# SparkFun_RTK_Facet_-_External_Connector.net
KiCad netlist of a schematic drawn in EAGLE
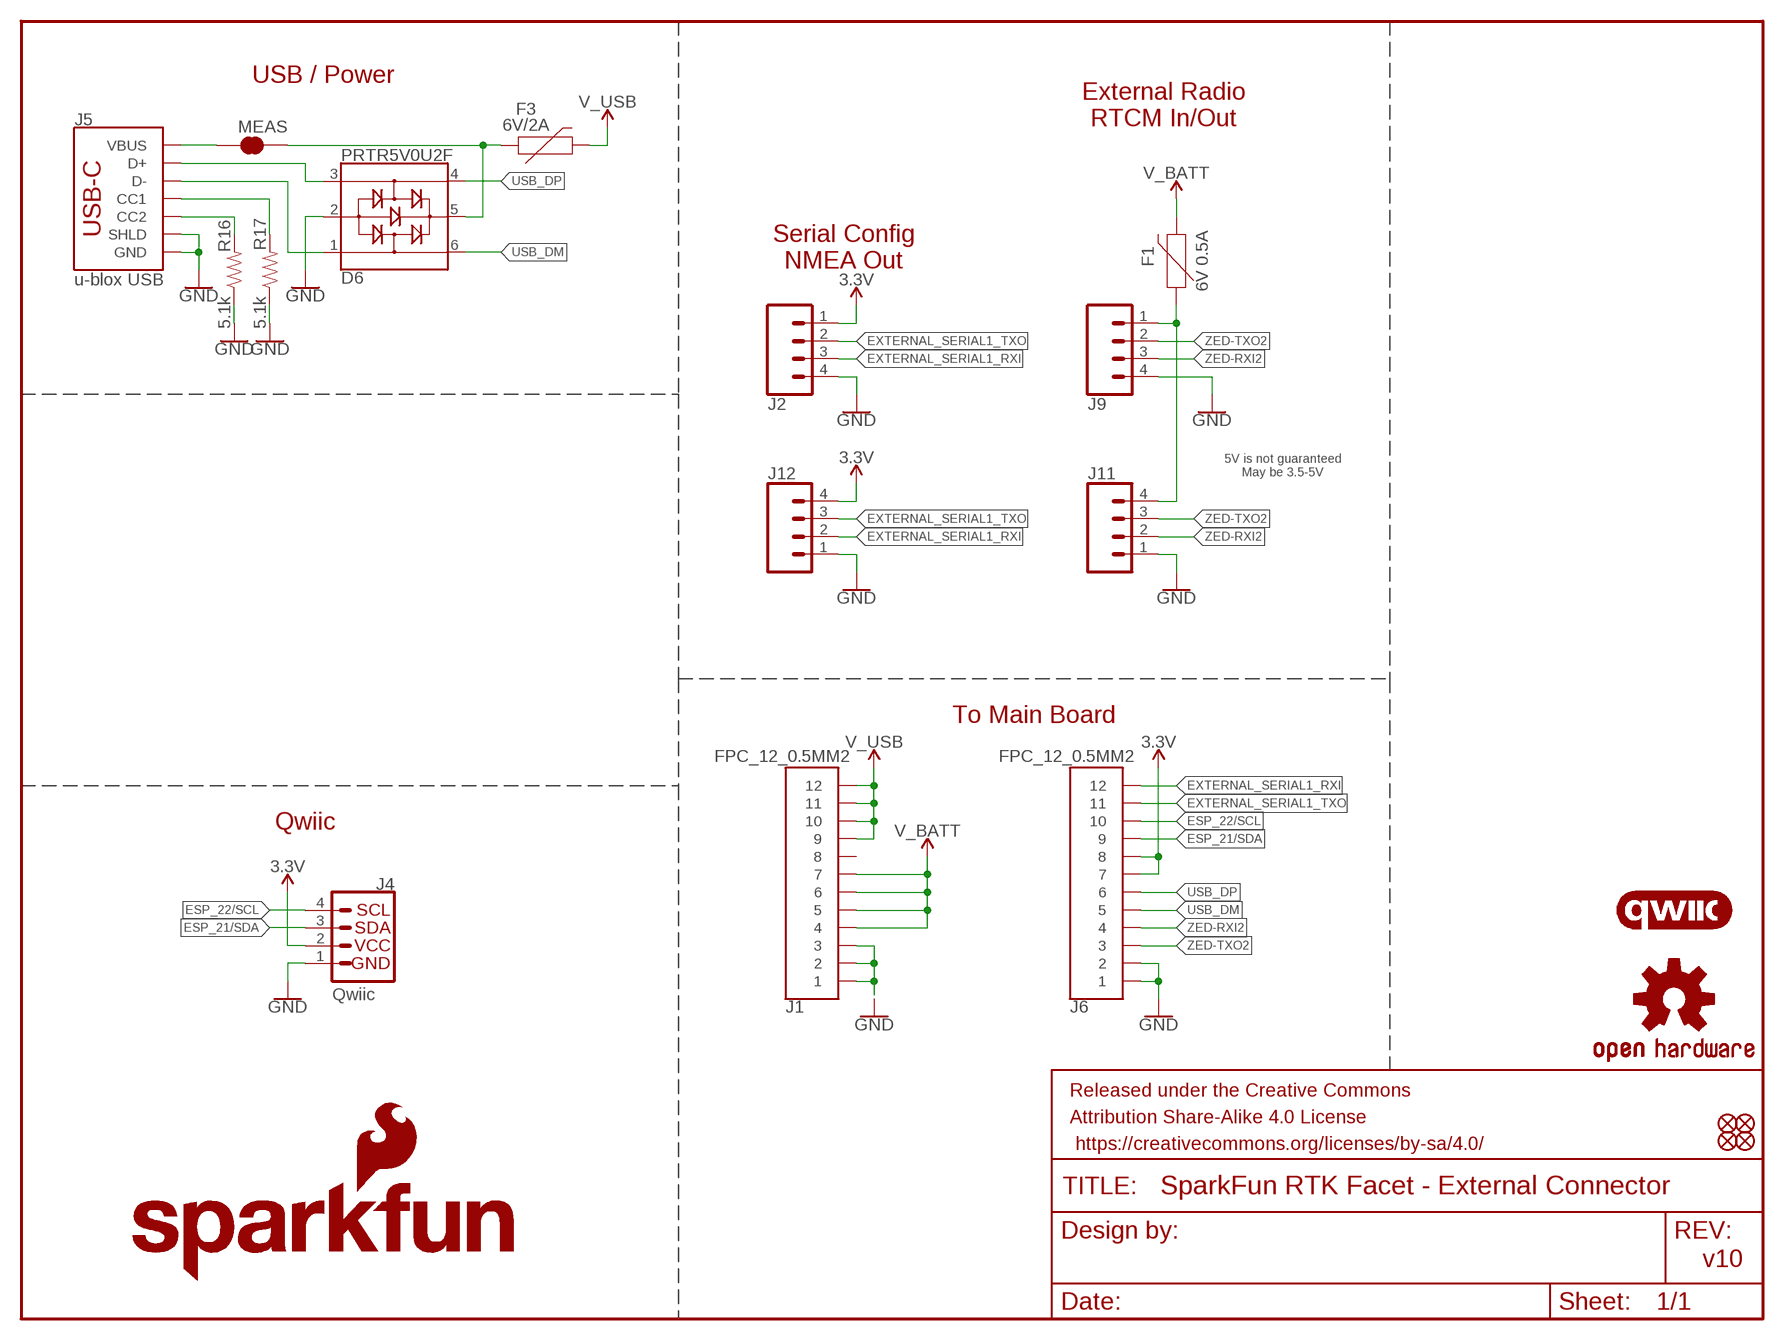
[diagram p0: schematic, sheet 1]

(export (version "E")
  (design (tool "Eeschema 10.0.6"))
  (components
    (comp (ref "D6")
      (value "PRTR5V0U2F")
      (footprint "eagle-import:SOT886")
      (libsource (lib "eagle-import") (part "PRTR5V0U2F"))
    )
    (comp (ref "F1")
      (value "6V 0.5A")
      (footprint "eagle-import:0805")
      (libsource (lib "eagle-import") (part "PPTC_6V500MA"))
    )
    (comp (ref "F3")
      (value "6V/2A")
      (footprint "eagle-import:1210")
      (libsource (lib "eagle-import") (part "PPTC_6V2A"))
    )
    (comp (ref "FRAME1")
      (value "FRAME-LETTER")
      (footprint "eagle-import:CREATIVE_COMMONS")
      (libsource (lib "eagle-import") (part "FRAME-LETTER"))
    )
    (comp (ref "J1")
      (value "FPC_12_0.5MM2")
      (footprint "eagle-import:FPC_12_FLIP_DOUBLESIDED_2")
      (libsource (lib "eagle-import") (part "FPC_12_0.5MM2"))
    )
    (comp (ref "J2")
      (value "CONN_04JST-SMD-LOCKING")
      (footprint "eagle-import:JST-4-SMD-1.25MM-LOCKING")
      (libsource (lib "eagle-import") (part "CONN_04JST-SMD-LOCKING"))
    )
    (comp (ref "J4")
      (value "Qwiic")
      (footprint "eagle-import:JST04_1MM_RA")
      (libsource (lib "eagle-import") (part "I2C_STANDARDQWIIC"))
    )
    (comp (ref "J5")
      (value "u-blox USB")
      (footprint "eagle-import:USB-C-16P-2LAYER-PADS")
      (libsource (lib "eagle-import") (part "USB_C_2-LAYER_PADS"))
    )
    (comp (ref "J6")
      (value "FPC_12_0.5MM2")
      (footprint "eagle-import:FPC_12_FLIP_DOUBLESIDED_2")
      (libsource (lib "eagle-import") (part "FPC_12_0.5MM2"))
    )
    (comp (ref "J9")
      (value "CONN_04JST-SMD-LOCKING")
      (footprint "eagle-import:JST-4-SMD-1.25MM-LOCKING")
      (libsource (lib "eagle-import") (part "CONN_04JST-SMD-LOCKING"))
    )
    (comp (ref "J11")
      (value "CONN_041X04_NO_SILK_NO_POP")
      (footprint "eagle-import:1X04_NO_SILK")
      (libsource (lib "eagle-import") (part "CONN_041X04_NO_SILK_NO_POP"))
    )
    (comp (ref "J12")
      (value "CONN_041X04_NO_SILK_NO_POP")
      (footprint "eagle-import:1X04_NO_SILK")
      (libsource (lib "eagle-import") (part "CONN_041X04_NO_SILK_NO_POP"))
    )
    (comp (ref "JP21")
      (value "FIDUCIALUFIDUCIAL")
      (footprint "eagle-import:FIDUCIAL-MICRO")
      (libsource (lib "eagle-import") (part "FIDUCIALUFIDUCIAL"))
    )
    (comp (ref "JP61")
      (value "FIDUCIALUFIDUCIAL")
      (footprint "eagle-import:FIDUCIAL-MICRO")
      (libsource (lib "eagle-import") (part "FIDUCIALUFIDUCIAL"))
    )
    (comp (ref "JP71")
      (value "FIDUCIALUFIDUCIAL")
      (footprint "eagle-import:FIDUCIAL-MICRO")
      (libsource (lib "eagle-import") (part "FIDUCIALUFIDUCIAL"))
    )
    (comp (ref "JP81")
      (value "FIDUCIALUFIDUCIAL")
      (footprint "eagle-import:FIDUCIAL-MICRO")
      (libsource (lib "eagle-import") (part "FIDUCIALUFIDUCIAL"))
    )
    (comp (ref "LOGO1")
      (value "OSHW-LOGOMINI")
      (footprint "eagle-import:OSHW-LOGO-MINI")
      (libsource (lib "eagle-import") (part "OSHW-LOGOMINI"))
    )
    (comp (ref "LOGO2")
      (value "SFE_LOGO_NAME_FLAME.1_INCH")
      (footprint "eagle-import:SFE_LOGO_NAME_FLAME_.1")
      (libsource (lib "eagle-import") (part "SFE_LOGO_NAME_FLAME.1_INCH"))
    )
    (comp (ref "LOGO3")
      (value "QWIIC_LOGO_CONNECTOR")
      (footprint "eagle-import:QWIIC_5.5MM")
      (libsource (lib "eagle-import") (part "QWIIC_LOGO_CONNECTOR"))
    )
    (comp (ref "MEAS")
      (value "JUMPER-COMBO_2_NC_TRACE")
      (footprint "eagle-import:COMBO-JUMPER_2_NC_TRACE")
      (libsource (lib "eagle-import") (part "JUMPER-COMBO_2_NC_TRACE"))
    )
    (comp (ref "R16")
      (value "5.1k")
      (footprint "eagle-import:0603")
      (libsource (lib "eagle-import") (part "5.1KOHM5.1KOHM-0603-1/10W-1%"))
    )
    (comp (ref "R17")
      (value "5.1k")
      (footprint "eagle-import:0603")
      (libsource (lib "eagle-import") (part "5.1KOHM5.1KOHM-0603-1/10W-1%"))
    )
  )
  (nets
    (net (code "1") (name "3.3V") (class "Default")
      (node (ref "J12") (pin "4") (pinfunction "4_4") (pintype "passive"))
      (node (ref "J2") (pin "1") (pinfunction "1_1") (pintype "passive"))
      (node (ref "J4") (pin "2") (pinfunction "2_2") (pintype "power_in"))
      (node (ref "J6") (pin "7") (pinfunction "7_7") (pintype "bidirectional"))
      (node (ref "J6") (pin "8") (pinfunction "8_8") (pintype "bidirectional"))
    )
    (net (code "2") (name "ESP_21{slash}SDA") (class "Default")
      (node (ref "J4") (pin "3") (pinfunction "3_3") (pintype "passive"))
      (node (ref "J6") (pin "9") (pinfunction "9_9") (pintype "bidirectional"))
    )
    (net (code "3") (name "ESP_22{slash}SCL") (class "Default")
      (node (ref "J4") (pin "4") (pinfunction "4_4") (pintype "passive"))
      (node (ref "J6") (pin "10") (pinfunction "10_10") (pintype "bidirectional"))
    )
    (net (code "4") (name "EXTERNAL_SERIAL1_RXI") (class "Default")
      (node (ref "J12") (pin "2") (pinfunction "2_2") (pintype "passive"))
      (node (ref "J2") (pin "3") (pinfunction "3_3") (pintype "passive"))
      (node (ref "J6") (pin "12") (pinfunction "12_12") (pintype "bidirectional"))
    )
    (net (code "5") (name "EXTERNAL_SERIAL1_TXO") (class "Default")
      (node (ref "J12") (pin "3") (pinfunction "3_3") (pintype "passive"))
      (node (ref "J2") (pin "2") (pinfunction "2_2") (pintype "passive"))
      (node (ref "J6") (pin "11") (pinfunction "11_11") (pintype "bidirectional"))
    )
    (net (code "6") (name "GND") (class "Default")
      (node (ref "D6") (pin "2") (pinfunction "2_2") (pintype "power_in"))
      (node (ref "J1") (pin "1") (pinfunction "1_1") (pintype "bidirectional"))
      (node (ref "J1") (pin "2") (pinfunction "2_2") (pintype "bidirectional"))
      (node (ref "J1") (pin "3") (pinfunction "3_3") (pintype "bidirectional"))
      (node (ref "J11") (pin "1") (pinfunction "1_1") (pintype "passive"))
      (node (ref "J12") (pin "1") (pinfunction "1_1") (pintype "passive"))
      (node (ref "J2") (pin "4") (pinfunction "4_4") (pintype "passive"))
      (node (ref "J4") (pin "1") (pinfunction "1_1") (pintype "power_in"))
      (node (ref "J5") (pin "GND") (pinfunction "GND_GND") (pintype "bidirectional"))
      (node (ref "J5") (pin "GND2") (pinfunction "GND_GND2") (pintype "bidirectional"))
      (node (ref "J5") (pin "SHLD1") (pinfunction "SHLD_SHLD1") (pintype "bidirectional"))
      (node (ref "J5") (pin "SHLD2") (pinfunction "SHLD_SHLD2") (pintype "bidirectional"))
      (node (ref "J5") (pin "SHLD3") (pinfunction "SHLD_SHLD3") (pintype "bidirectional"))
      (node (ref "J5") (pin "SHLD4") (pinfunction "SHLD_SHLD4") (pintype "bidirectional"))
      (node (ref "J6") (pin "1") (pinfunction "1_1") (pintype "bidirectional"))
      (node (ref "J6") (pin "2") (pinfunction "2_2") (pintype "bidirectional"))
      (node (ref "J9") (pin "4") (pinfunction "4_4") (pintype "passive"))
      (node (ref "R16") (pin "1") (pinfunction "1_1") (pintype "passive"))
      (node (ref "R17") (pin "1") (pinfunction "1_1") (pintype "passive"))
    )
    (net (code "7") (name "Net-(D6-Pad1)") (class "Default")
      (node (ref "D6") (pin "1") (pinfunction "1_1") (pintype "bidirectional"))
      (node (ref "J5") (pin "A7") (pinfunction "D-_A7") (pintype "bidirectional"))
      (node (ref "J5") (pin "B7") (pinfunction "D-_B7") (pintype "bidirectional"))
    )
    (net (code "8") (name "Net-(D6-Pad3)") (class "Default")
      (node (ref "D6") (pin "3") (pinfunction "3_3") (pintype "bidirectional"))
      (node (ref "J5") (pin "A6") (pinfunction "D+_A6") (pintype "bidirectional"))
      (node (ref "J5") (pin "B6") (pinfunction "D+_B6") (pintype "bidirectional"))
    )
    (net (code "9") (name "Net-(D6-Pad5)") (class "Default")
      (node (ref "D6") (pin "5") (pinfunction "5_5") (pintype "power_in"))
      (node (ref "F3") (pin "1") (pinfunction "1_1") (pintype "bidirectional"))
      (node (ref "MEAS") (pin "2") (pinfunction "2_2") (pintype "passive"))
      (node (ref "MEAS") (pin "4") (pinfunction "2_4") (pintype "passive"))
    )
    (net (code "10") (name "Net-(F1-Pad1)") (class "Default")
      (node (ref "F1") (pin "1") (pinfunction "1_1") (pintype "bidirectional"))
      (node (ref "J11") (pin "4") (pinfunction "4_4") (pintype "passive"))
      (node (ref "J9") (pin "1") (pinfunction "1_1") (pintype "passive"))
    )
    (net (code "11") (name "Net-(J5-CC1)") (class "Default")
      (node (ref "J5") (pin "A5") (pinfunction "CC1_A5") (pintype "bidirectional"))
      (node (ref "R17") (pin "2") (pinfunction "2_2") (pintype "passive"))
    )
    (net (code "12") (name "Net-(J5-CC2)") (class "Default")
      (node (ref "J5") (pin "B5") (pinfunction "CC2_B5") (pintype "bidirectional"))
      (node (ref "R16") (pin "2") (pinfunction "2_2") (pintype "passive"))
    )
    (net (code "13") (name "Net-(J5-VBUS-PadVBUS1)") (class "Default")
      (node (ref "J5") (pin "VBUS1") (pinfunction "VBUS_VBUS1") (pintype "bidirectional"))
      (node (ref "J5") (pin "VBUS2") (pinfunction "VBUS_VBUS2") (pintype "bidirectional"))
      (node (ref "MEAS") (pin "1") (pinfunction "1_1") (pintype "passive"))
      (node (ref "MEAS") (pin "3") (pinfunction "1_3") (pintype "passive"))
    )
    (net (code "14") (name "USB_DM") (class "Default")
      (node (ref "D6") (pin "6") (pinfunction "6_6") (pintype "bidirectional"))
      (node (ref "J6") (pin "5") (pinfunction "5_5") (pintype "bidirectional"))
    )
    (net (code "15") (name "USB_DP") (class "Default")
      (node (ref "D6") (pin "4") (pinfunction "4_4") (pintype "bidirectional"))
      (node (ref "J6") (pin "6") (pinfunction "6_6") (pintype "bidirectional"))
    )
    (net (code "16") (name "V_BATT") (class "Default")
      (node (ref "F1") (pin "2") (pinfunction "2_2") (pintype "bidirectional"))
      (node (ref "J1") (pin "4") (pinfunction "4_4") (pintype "bidirectional"))
      (node (ref "J1") (pin "5") (pinfunction "5_5") (pintype "bidirectional"))
      (node (ref "J1") (pin "6") (pinfunction "6_6") (pintype "bidirectional"))
      (node (ref "J1") (pin "7") (pinfunction "7_7") (pintype "bidirectional"))
    )
    (net (code "17") (name "V_USB") (class "Default")
      (node (ref "F3") (pin "2") (pinfunction "2_2") (pintype "bidirectional"))
      (node (ref "J1") (pin "10") (pinfunction "10_10") (pintype "bidirectional"))
      (node (ref "J1") (pin "11") (pinfunction "11_11") (pintype "bidirectional"))
      (node (ref "J1") (pin "12") (pinfunction "12_12") (pintype "bidirectional"))
      (node (ref "J1") (pin "9") (pinfunction "9_9") (pintype "bidirectional"))
    )
    (net (code "18") (name "ZED-RXI2") (class "Default")
      (node (ref "J11") (pin "2") (pinfunction "2_2") (pintype "passive"))
      (node (ref "J6") (pin "4") (pinfunction "4_4") (pintype "bidirectional"))
      (node (ref "J9") (pin "3") (pinfunction "3_3") (pintype "passive"))
    )
    (net (code "19") (name "ZED-TXO2") (class "Default")
      (node (ref "J11") (pin "3") (pinfunction "3_3") (pintype "passive"))
      (node (ref "J6") (pin "3") (pinfunction "3_3") (pintype "bidirectional"))
      (node (ref "J9") (pin "2") (pinfunction "2_2") (pintype "passive"))
    )
    (net (code "20") (name "unconnected-(J1-Pad8)") (class "Default")
      (node (ref "J1") (pin "8") (pinfunction "8_8") (pintype "bidirectional"))
    )
  )
)
